# PROB_S7CAS_INTERFACE.net
KiCad netlist of a schematic drawn in Altium Designer
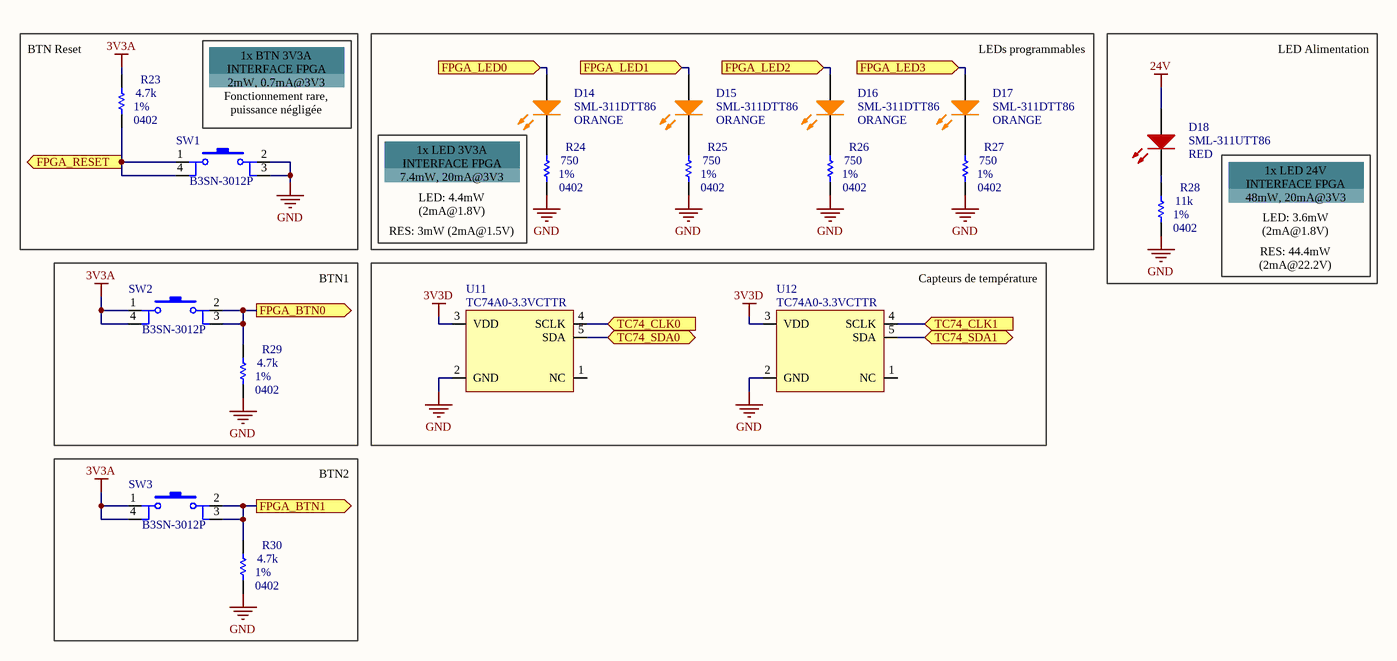
[diagram p0: PROB_S7CAS_INTERFACE.SchDoc]

(export (version "E")
  (design (tool "Eeschema 10.0.6"))
  (components
    (comp (ref "D14")
      (value "SML-311DTT86")
      (footprint "LED_0603")
      (description "LED - 611nM ORANGE 2mA - 0603")
      (fields
        (field (name "VOLTAGE") "1.8V")
        (field (name "MFG") "ROHM Semiconductor")
        (field (name "ALTIUM_VALUE") "ORANGE")
        (field (name "CREATEDBY") "Jonathan Bouchard")
      )
      (libsource (lib "S7CAS_LIB2021") (part "LED_SML-311DTT86"))
    )
    (comp (ref "D15")
      (value "SML-311DTT86")
      (footprint "LED_0603")
      (description "LED - 611nM ORANGE 2mA - 0603")
      (fields
        (field (name "VOLTAGE") "1.8V")
        (field (name "MFG") "ROHM Semiconductor")
        (field (name "ALTIUM_VALUE") "ORANGE")
        (field (name "CREATEDBY") "Jonathan Bouchard")
      )
      (libsource (lib "S7CAS_LIB2021") (part "LED_SML-311DTT86"))
    )
    (comp (ref "D16")
      (value "SML-311DTT86")
      (footprint "LED_0603")
      (description "LED - 611nM ORANGE 2mA - 0603")
      (fields
        (field (name "VOLTAGE") "1.8V")
        (field (name "MFG") "ROHM Semiconductor")
        (field (name "ALTIUM_VALUE") "ORANGE")
        (field (name "CREATEDBY") "Jonathan Bouchard")
      )
      (libsource (lib "S7CAS_LIB2021") (part "LED_SML-311DTT86"))
    )
    (comp (ref "D17")
      (value "SML-311DTT86")
      (footprint "LED_0603")
      (description "LED - 611nM ORANGE 2mA - 0603")
      (fields
        (field (name "VOLTAGE") "1.8V")
        (field (name "MFG") "ROHM Semiconductor")
        (field (name "ALTIUM_VALUE") "ORANGE")
        (field (name "CREATEDBY") "Jonathan Bouchard")
      )
      (libsource (lib "S7CAS_LIB2021") (part "LED_SML-311DTT86"))
    )
    (comp (ref "D18")
      (value "SML-311UTT86")
      (footprint "LED_0603")
      (description "LED - 620nM RED 2mA - 0603")
      (fields
        (field (name "VOLTAGE") "1.8V")
        (field (name "MFG") "ROHM Semiconductor")
        (field (name "ALTIUM_VALUE") "RED")
        (field (name "CREATEDBY") "Jonathan Bouchard")
      )
      (libsource (lib "S7CAS_LIB2021") (part "LED_SML-311UTT86"))
    )
    (comp (ref "R23")
      (value "4.7k")
      (footprint "RES_0402")
      (description "RES - 0402")
      (fields
        (field (name "VOLTAGE") "50V")
        (field (name "POWER") "1/16W")
        (field (name "PACKAGE") "0402")
        (field (name "PRECISION") "1%")
        (field (name "CREATEDBY") "Jonathan Bouchard")
      )
      (libsource (lib "S7CAS_LIB2021") (part "RES - 0402"))
    )
    (comp (ref "R24")
      (value "750")
      (footprint "RES_0402")
      (description "RES - 0402")
      (fields
        (field (name "VOLTAGE") "50V")
        (field (name "POWER") "1/16W")
        (field (name "PACKAGE") "0402")
        (field (name "PRECISION") "1%")
        (field (name "CREATEDBY") "Jonathan Bouchard")
      )
      (libsource (lib "S7CAS_LIB2021") (part "RES - 0402"))
    )
    (comp (ref "R25")
      (value "750")
      (footprint "RES_0402")
      (description "RES - 0402")
      (fields
        (field (name "VOLTAGE") "50V")
        (field (name "POWER") "1/16W")
        (field (name "PACKAGE") "0402")
        (field (name "PRECISION") "1%")
        (field (name "CREATEDBY") "Jonathan Bouchard")
      )
      (libsource (lib "S7CAS_LIB2021") (part "RES - 0402"))
    )
    (comp (ref "R26")
      (value "750")
      (footprint "RES_0402")
      (description "RES - 0402")
      (fields
        (field (name "VOLTAGE") "50V")
        (field (name "POWER") "1/16W")
        (field (name "PACKAGE") "0402")
        (field (name "PRECISION") "1%")
        (field (name "CREATEDBY") "Jonathan Bouchard")
      )
      (libsource (lib "S7CAS_LIB2021") (part "RES - 0402"))
    )
    (comp (ref "R27")
      (value "750")
      (footprint "RES_0402")
      (description "RES - 0402")
      (fields
        (field (name "VOLTAGE") "50V")
        (field (name "POWER") "1/16W")
        (field (name "PACKAGE") "0402")
        (field (name "PRECISION") "1%")
        (field (name "CREATEDBY") "Jonathan Bouchard")
      )
      (libsource (lib "S7CAS_LIB2021") (part "RES - 0402"))
    )
    (comp (ref "R28")
      (value "11k")
      (footprint "RES_0402")
      (description "RES - 0402")
      (fields
        (field (name "VOLTAGE") "50V")
        (field (name "POWER") "1/16W")
        (field (name "PACKAGE") "0402")
        (field (name "PRECISION") "1%")
        (field (name "CREATEDBY") "Jonathan Bouchard")
      )
      (libsource (lib "S7CAS_LIB2021") (part "RES - 0402"))
    )
    (comp (ref "R29")
      (value "4.7k")
      (footprint "RES_0402")
      (description "RES - 0402")
      (fields
        (field (name "VOLTAGE") "50V")
        (field (name "POWER") "1/16W")
        (field (name "PACKAGE") "0402")
        (field (name "PRECISION") "1%")
        (field (name "CREATEDBY") "Jonathan Bouchard")
      )
      (libsource (lib "S7CAS_LIB2021") (part "RES - 0402"))
    )
    (comp (ref "R30")
      (value "4.7k")
      (footprint "RES_0402")
      (description "RES - 0402")
      (fields
        (field (name "VOLTAGE") "50V")
        (field (name "POWER") "1/16W")
        (field (name "PACKAGE") "0402")
        (field (name "PRECISION") "1%")
        (field (name "CREATEDBY") "Jonathan Bouchard")
      )
      (libsource (lib "S7CAS_LIB2021") (part "RES - 0402"))
    )
    (comp (ref "SW1")
      (value "B3SN-3012P")
      (footprint "SWI_TACT_B3SN-3012P")
      (description "SWI - TACT SPST-NO 0.05A 24V - 4-SMD")
      (fields
        (field (name "MFG") "Omron")
        (field (name "VOLTAGE") "24V")
        (field (name "CREATEDBY") "Jonathan Bouchard")
      )
      (libsource (lib "S7CAS_LIB2021") (part "SWI_TACT_B3SN-3012P"))
    )
    (comp (ref "SW2")
      (value "B3SN-3012P")
      (footprint "SWI_TACT_B3SN-3012P")
      (description "SWI - TACT SPST-NO 0.05A 24V - 4-SMD")
      (fields
        (field (name "MFG") "Omron")
        (field (name "VOLTAGE") "24V")
        (field (name "CREATEDBY") "Jonathan Bouchard")
      )
      (libsource (lib "S7CAS_LIB2021") (part "SWI_TACT_B3SN-3012P"))
    )
    (comp (ref "SW3")
      (value "B3SN-3012P")
      (footprint "SWI_TACT_B3SN-3012P")
      (description "SWI - TACT SPST-NO 0.05A 24V - 4-SMD")
      (fields
        (field (name "MFG") "Omron")
        (field (name "VOLTAGE") "24V")
        (field (name "CREATEDBY") "Jonathan Bouchard")
      )
      (libsource (lib "S7CAS_LIB2021") (part "SWI_TACT_B3SN-3012P"))
    )
    (comp (ref "U11")
      (value "TC74A0-3.3VCTTR")
      (footprint "SEN_TEMP_TC74A0-3.3VCTTR")
      (description "SENS - TEMPERATURE SENSOR I2C/SMBUS - SOT23-5")
      (fields
        (field (name "VOLTAGE") "2.7 V ~ 5.5 V")
        (field (name "MFG") "Microchip")
        (field (name "CREATEDBY") "Jonathan Bouchard")
      )
      (libsource (lib "S7CAS_LIB2021") (part "SENS_TEMP_TC74A0-3.3VCTTR"))
    )
    (comp (ref "U12")
      (value "TC74A0-3.3VCTTR")
      (footprint "SEN_TEMP_TC74A0-3.3VCTTR")
      (description "SENS - TEMPERATURE SENSOR I2C/SMBUS - SOT23-5")
      (fields
        (field (name "VOLTAGE") "2.7 V ~ 5.5 V")
        (field (name "MFG") "Microchip")
        (field (name "CREATEDBY") "Jonathan Bouchard")
      )
      (libsource (lib "S7CAS_LIB2021") (part "SENS_TEMP_TC74A0-3.3VCTTR"))
    )
  )
  (nets
    (net (code "1") (name "/FPGA_BTN0") (class "Default")
      (node (ref "R29") (pin "2") (pinfunction "2_2") (pintype "passive"))
      (node (ref "SW2") (pin "2") (pinfunction "2_2") (pintype "passive"))
      (node (ref "SW2") (pin "3") (pinfunction "3_3") (pintype "passive"))
    )
    (net (code "2") (name "/FPGA_BTN1") (class "Default")
      (node (ref "R30") (pin "2") (pinfunction "2_2") (pintype "passive"))
      (node (ref "SW3") (pin "2") (pinfunction "2_2") (pintype "passive"))
      (node (ref "SW3") (pin "3") (pinfunction "3_3") (pintype "passive"))
    )
    (net (code "3") (name "/FPGA_LED0") (class "Default")
      (node (ref "D14") (pin "A") (pinfunction "A_A") (pintype "passive"))
    )
    (net (code "4") (name "/FPGA_LED1") (class "Default")
      (node (ref "D15") (pin "A") (pinfunction "A_A") (pintype "passive"))
    )
    (net (code "5") (name "/FPGA_LED2") (class "Default")
      (node (ref "D16") (pin "A") (pinfunction "A_A") (pintype "passive"))
    )
    (net (code "6") (name "/FPGA_LED3") (class "Default")
      (node (ref "D17") (pin "A") (pinfunction "A_A") (pintype "passive"))
    )
    (net (code "7") (name "/FPGA_RESET") (class "Default")
      (node (ref "R23") (pin "1") (pinfunction "1_1") (pintype "passive"))
      (node (ref "SW1") (pin "1") (pinfunction "1_1") (pintype "passive"))
      (node (ref "SW1") (pin "4") (pinfunction "4_4") (pintype "passive"))
    )
    (net (code "8") (name "/TC74_CLK0") (class "Default")
      (node (ref "U11") (pin "4") (pinfunction "SCLK_4") (pintype "passive"))
    )
    (net (code "9") (name "/TC74_CLK1") (class "Default")
      (node (ref "U12") (pin "4") (pinfunction "SCLK_4") (pintype "passive"))
    )
    (net (code "10") (name "/TC74_SDA0") (class "Default")
      (node (ref "U11") (pin "5") (pinfunction "SDA_5") (pintype "passive"))
    )
    (net (code "11") (name "/TC74_SDA1") (class "Default")
      (node (ref "U12") (pin "5") (pinfunction "SDA_5") (pintype "passive"))
    )
    (net (code "12") (name "3V3A") (class "Default")
      (node (ref "R23") (pin "2") (pinfunction "2_2") (pintype "passive"))
      (node (ref "SW2") (pin "1") (pinfunction "1_1") (pintype "passive"))
      (node (ref "SW2") (pin "4") (pinfunction "4_4") (pintype "passive"))
      (node (ref "SW3") (pin "1") (pinfunction "1_1") (pintype "passive"))
      (node (ref "SW3") (pin "4") (pinfunction "4_4") (pintype "passive"))
    )
    (net (code "13") (name "3V3D") (class "Default")
      (node (ref "U11") (pin "3") (pinfunction "VDD_3") (pintype "passive"))
      (node (ref "U12") (pin "3") (pinfunction "VDD_3") (pintype "passive"))
    )
    (net (code "14") (name "24V") (class "Default")
      (node (ref "D18") (pin "A") (pinfunction "A_A") (pintype "passive"))
    )
    (net (code "15") (name "GND") (class "Default")
      (node (ref "R24") (pin "1") (pinfunction "1_1") (pintype "passive"))
      (node (ref "R25") (pin "1") (pinfunction "1_1") (pintype "passive"))
      (node (ref "R26") (pin "1") (pinfunction "1_1") (pintype "passive"))
      (node (ref "R27") (pin "1") (pinfunction "1_1") (pintype "passive"))
      (node (ref "R28") (pin "1") (pinfunction "1_1") (pintype "passive"))
      (node (ref "R29") (pin "1") (pinfunction "1_1") (pintype "passive"))
      (node (ref "R30") (pin "1") (pinfunction "1_1") (pintype "passive"))
      (node (ref "SW1") (pin "2") (pinfunction "2_2") (pintype "passive"))
      (node (ref "SW1") (pin "3") (pinfunction "3_3") (pintype "passive"))
      (node (ref "U11") (pin "2") (pinfunction "GND_2") (pintype "passive"))
      (node (ref "U12") (pin "2") (pinfunction "GND_2") (pintype "passive"))
    )
    (net (code "16") (name "Net-(D14-PadK)") (class "Default")
      (node (ref "D14") (pin "K") (pinfunction "K_K") (pintype "passive"))
      (node (ref "R24") (pin "2") (pinfunction "2_2") (pintype "passive"))
    )
    (net (code "17") (name "Net-(D15-PadK)") (class "Default")
      (node (ref "D15") (pin "K") (pinfunction "K_K") (pintype "passive"))
      (node (ref "R25") (pin "2") (pinfunction "2_2") (pintype "passive"))
    )
    (net (code "18") (name "Net-(D16-PadK)") (class "Default")
      (node (ref "D16") (pin "K") (pinfunction "K_K") (pintype "passive"))
      (node (ref "R26") (pin "2") (pinfunction "2_2") (pintype "passive"))
    )
    (net (code "19") (name "Net-(D17-PadK)") (class "Default")
      (node (ref "D17") (pin "K") (pinfunction "K_K") (pintype "passive"))
      (node (ref "R27") (pin "2") (pinfunction "2_2") (pintype "passive"))
    )
    (net (code "20") (name "Net-(D18-PadK)") (class "Default")
      (node (ref "D18") (pin "K") (pinfunction "K_K") (pintype "passive"))
      (node (ref "R28") (pin "2") (pinfunction "2_2") (pintype "passive"))
    )
    (net (code "21") (name "unconnected-(U11-NC-Pad1)") (class "Default")
      (node (ref "U11") (pin "1") (pinfunction "NC_1") (pintype "passive"))
    )
    (net (code "22") (name "unconnected-(U12-NC-Pad1)") (class "Default")
      (node (ref "U12") (pin "1") (pinfunction "NC_1") (pintype "passive"))
    )
  )
)
